# USB_to_UART.net
KiCad netlist of a schematic drawn in Altium Designer
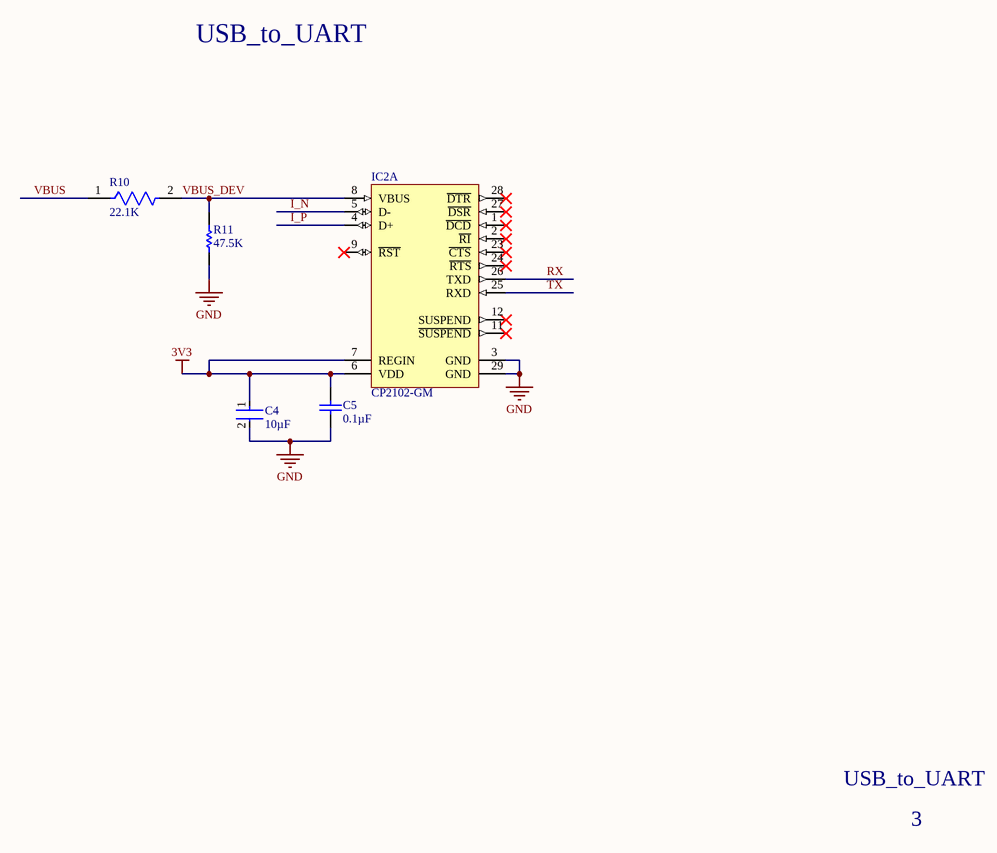
[diagram p0: USB_to_UART.SchDoc]

(export (version "E")
  (design (tool "Eeschema 10.0.6"))
  (components
    (comp (ref "C4")
      (value "10µF")
      (footprint "FP-CC0603-0_15-0_95-IPC_B")
      (description "CAP CER 10UF 6.3V X5R 0603")
      (fields (field (name "TOLERANCE") "20%") (field (name "VOLTAGE") "4V"))
      (libsource (lib "Altium Content Vault") (part "02cd4be3c70576c341d710602a673aa"))
    )
    (comp (ref "C5")
      (value "0.1µF")
      (footprint "CAPC1608X87X35NL15T15")
      (fields (field (name "PART NUMBER") "C0603C104K9RACTU") (field (name "MANUFACTURER") "Kemet"))
      (libsource (lib "Altium Content Vault") (part "CAP"))
    )
    (comp (ref "IC2")
      (value "CP2102-GM")
      (footprint "SLAB-QFN-28-3125x3125TP_N")
      (description "Single-Chip USB to UART Bridge, 1024 Bytes EEPROM, -40 to 85 degC, 28-pin QFN, Tube")
      (fields (field (name "MANUFACTURER") "Silicon Labs"))
      (libsource (lib "Altium Content Vault") (part "SLAB-CP210X-QFN-28-29"))
    )
    (comp (ref "R10")
      (value "22.1K")
      (footprint "FP-RC0603-0_55-MFG")
      (description "RES SMD 22.1K OHM 1% 1/10W 0603")
      (fields (field (name "TOLERANCE") "1%"))
      (libsource (lib "Altium Content Vault") (part "1029c3af85768c4190bb7ad29bc67b5"))
    )
    (comp (ref "R11")
      (value "47.5K")
      (footprint "RESC1608X55X30LL15T15")
      (fields (field (name "MANUFACTURER") "Panasonic") (field (name "PART NUMBER") "ERJ-3EKF4752V"))
      (libsource (lib "Altium Content Vault") (part "RES"))
    )
  )
  (nets
    (net (code "1") (name "/I_N") (class "Default")
      (node (ref "IC2") (pin "5") (pinfunction "D-_5") (pintype "bidirectional"))
    )
    (net (code "2") (name "/I_P") (class "Default")
      (node (ref "IC2") (pin "4") (pinfunction "D+_4") (pintype "bidirectional"))
    )
    (net (code "3") (name "/RX") (class "Default")
      (node (ref "IC2") (pin "26") (pinfunction "TXD_26") (pintype "output"))
    )
    (net (code "4") (name "/TX") (class "Default")
      (node (ref "IC2") (pin "25") (pinfunction "RXD_25") (pintype "input"))
    )
    (net (code "5") (name "/VBUS") (class "Default")
      (node (ref "R10") (pin "1") (pinfunction "1_1") (pintype "passive"))
    )
    (net (code "6") (name "/VBUS_DEV") (class "Default")
      (node (ref "IC2") (pin "8") (pinfunction "VBUS_8") (pintype "input"))
      (node (ref "R10") (pin "2") (pinfunction "2_2") (pintype "passive"))
      (node (ref "R11") (pin "2") (pinfunction "2_2") (pintype "passive"))
    )
    (net (code "7") (name "3V3") (class "Default")
      (node (ref "C4") (pin "1") (pinfunction "1_1") (pintype "passive"))
      (node (ref "C5") (pin "2") (pinfunction "2_2") (pintype "passive"))
      (node (ref "IC2") (pin "6") (pinfunction "VDD_6") (pintype "power_in"))
      (node (ref "IC2") (pin "7") (pinfunction "REGIN_7") (pintype "power_in"))
    )
    (net (code "8") (name "GND") (class "Default")
      (node (ref "C4") (pin "2") (pinfunction "2_2") (pintype "passive"))
      (node (ref "C5") (pin "1") (pinfunction "1_1") (pintype "passive"))
      (node (ref "IC2") (pin "29") (pinfunction "GND_29") (pintype "power_in"))
      (node (ref "IC2") (pin "3") (pinfunction "GND_3") (pintype "power_in"))
      (node (ref "R11") (pin "1") (pinfunction "1_1") (pintype "passive"))
    )
    (net (code "9") (name "unconnected-(IC2A-SUSPEND-Pad12)") (class "Default")
      (node (ref "IC2") (pin "12") (pinfunction "SUSPEND_12") (pintype "output+no_connect"))
    )
    (net (code "10") (name "unconnected-(IC2A-~{CTS}-Pad23)") (class "Default")
      (node (ref "IC2") (pin "23") (pinfunction "~{CTS}_23") (pintype "input+no_connect"))
    )
    (net (code "11") (name "unconnected-(IC2A-~{DCD}-Pad1)") (class "Default")
      (node (ref "IC2") (pin "1") (pinfunction "~{DCD}_1") (pintype "input+no_connect"))
    )
    (net (code "12") (name "unconnected-(IC2A-~{DSR}-Pad27)") (class "Default")
      (node (ref "IC2") (pin "27") (pinfunction "~{DSR}_27") (pintype "input+no_connect"))
    )
    (net (code "13") (name "unconnected-(IC2A-~{DTR}-Pad28)") (class "Default")
      (node (ref "IC2") (pin "28") (pinfunction "~{DTR}_28") (pintype "output+no_connect"))
    )
    (net (code "14") (name "unconnected-(IC2A-~{RI}-Pad2)") (class "Default")
      (node (ref "IC2") (pin "2") (pinfunction "~{RI}_2") (pintype "input+no_connect"))
    )
    (net (code "15") (name "unconnected-(IC2A-~{RST}-Pad9)") (class "Default")
      (node (ref "IC2") (pin "9") (pinfunction "~{RST}_9") (pintype "bidirectional+no_connect"))
    )
    (net (code "16") (name "unconnected-(IC2A-~{RTS}-Pad24)") (class "Default")
      (node (ref "IC2") (pin "24") (pinfunction "~{RTS}_24") (pintype "output+no_connect"))
    )
    (net (code "17") (name "unconnected-(IC2A-~{SUSPEND}-Pad11)") (class "Default")
      (node (ref "IC2") (pin "11") (pinfunction "~{SUSPEND}_11") (pintype "output+no_connect"))
    )
  )
)
